# NPN_CONNECTOR.net
KiCad netlist of a schematic drawn in Altium Designer
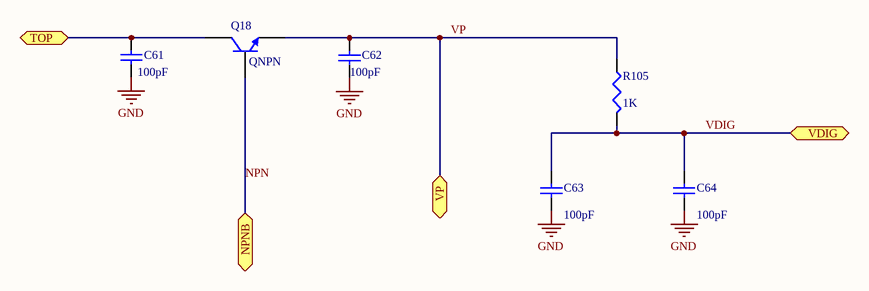
[diagram p0: NPN_CONNECTOR.SchDoc]

(export (version "E")
  (design (tool "Eeschema 10.0.6"))
  (components
    (comp (ref "C61")
      (value "100pF")
      (footprint "C1206")
      (description "Capacitor (Semiconductor SIM Model)")
      (fields (field (name "Comment") "Cap Semi") (field (name "PUBLISHER") "Altium Limited"))
      (libsource (lib "Miscellaneous Devices") (part "Cap Semi"))
    )
    (comp (ref "C62")
      (value "100pF")
      (footprint "C1206")
      (description "Capacitor (Semiconductor SIM Model)")
      (fields (field (name "Comment") "Cap Semi") (field (name "PUBLISHER") "Altium Limited"))
      (libsource (lib "Miscellaneous Devices") (part "Cap Semi"))
    )
    (comp (ref "C63")
      (value "100pF")
      (footprint "C1206")
      (description "Capacitor (Semiconductor SIM Model)")
      (fields (field (name "Comment") "Cap Semi") (field (name "PUBLISHER") "Altium Limited"))
      (libsource (lib "Miscellaneous Devices") (part "Cap Semi"))
    )
    (comp (ref "C64")
      (value "100pF")
      (footprint "C1206")
      (description "Capacitor (Semiconductor SIM Model)")
      (fields (field (name "Comment") "Cap Semi") (field (name "PUBLISHER") "Altium Limited"))
      (libsource (lib "Miscellaneous Devices") (part "Cap Semi"))
    )
    (comp (ref "Q18")
      (value "QNPN")
      (footprint "ZXTN4004KTCDICT-ND")
      (description "NPN Bipolar Transistor")
      (fields
        (field (name "MANUFACTURER") "Diodes")
        (field (name "MANUFACTURER PART NUMBER") "ZXTN4004KTC")
        (field (name "PUBLISHER") "Altium Limited")
      )
      (libsource (lib "Miscellaneous Devices") (part "QNPN"))
    )
    (comp (ref "R105")
      (value "1K")
      (footprint "J1-0603")
      (description "Resistor")
      (fields (field (name "Comment") "Res3") (field (name "PUBLISHER") "Altium Limited"))
      (libsource (lib "Miscellaneous Devices") (part "Res3"))
    )
  )
  (nets
    (net (code "1") (name "/NPN") (class "Default")
      (node (ref "Q18") (pin "2") (pinfunction "B_2") (pintype "passive"))
    )
    (net (code "2") (name "/TOP") (class "Default")
      (node (ref "C61") (pin "1") (pinfunction "1_1") (pintype "passive"))
      (node (ref "Q18") (pin "1") (pinfunction "C_1") (pintype "passive"))
    )
    (net (code "3") (name "/VDIG") (class "Default")
      (node (ref "C63") (pin "2") (pinfunction "2_2") (pintype "passive"))
      (node (ref "C64") (pin "2") (pinfunction "2_2") (pintype "passive"))
      (node (ref "R105") (pin "2") (pinfunction "2_2") (pintype "passive"))
    )
    (net (code "4") (name "/VP") (class "Default")
      (node (ref "C62") (pin "2") (pinfunction "2_2") (pintype "passive"))
      (node (ref "Q18") (pin "3") (pinfunction "E_3") (pintype "passive"))
      (node (ref "R105") (pin "1") (pinfunction "1_1") (pintype "passive"))
    )
    (net (code "5") (name "GND") (class "Default")
      (node (ref "C61") (pin "2") (pinfunction "2_2") (pintype "passive"))
      (node (ref "C62") (pin "1") (pinfunction "1_1") (pintype "passive"))
      (node (ref "C63") (pin "1") (pinfunction "1_1") (pintype "passive"))
      (node (ref "C64") (pin "1") (pinfunction "1_1") (pintype "passive"))
    )
  )
)
